# Digital.net
KiCad netlist of a schematic drawn in Altium Designer
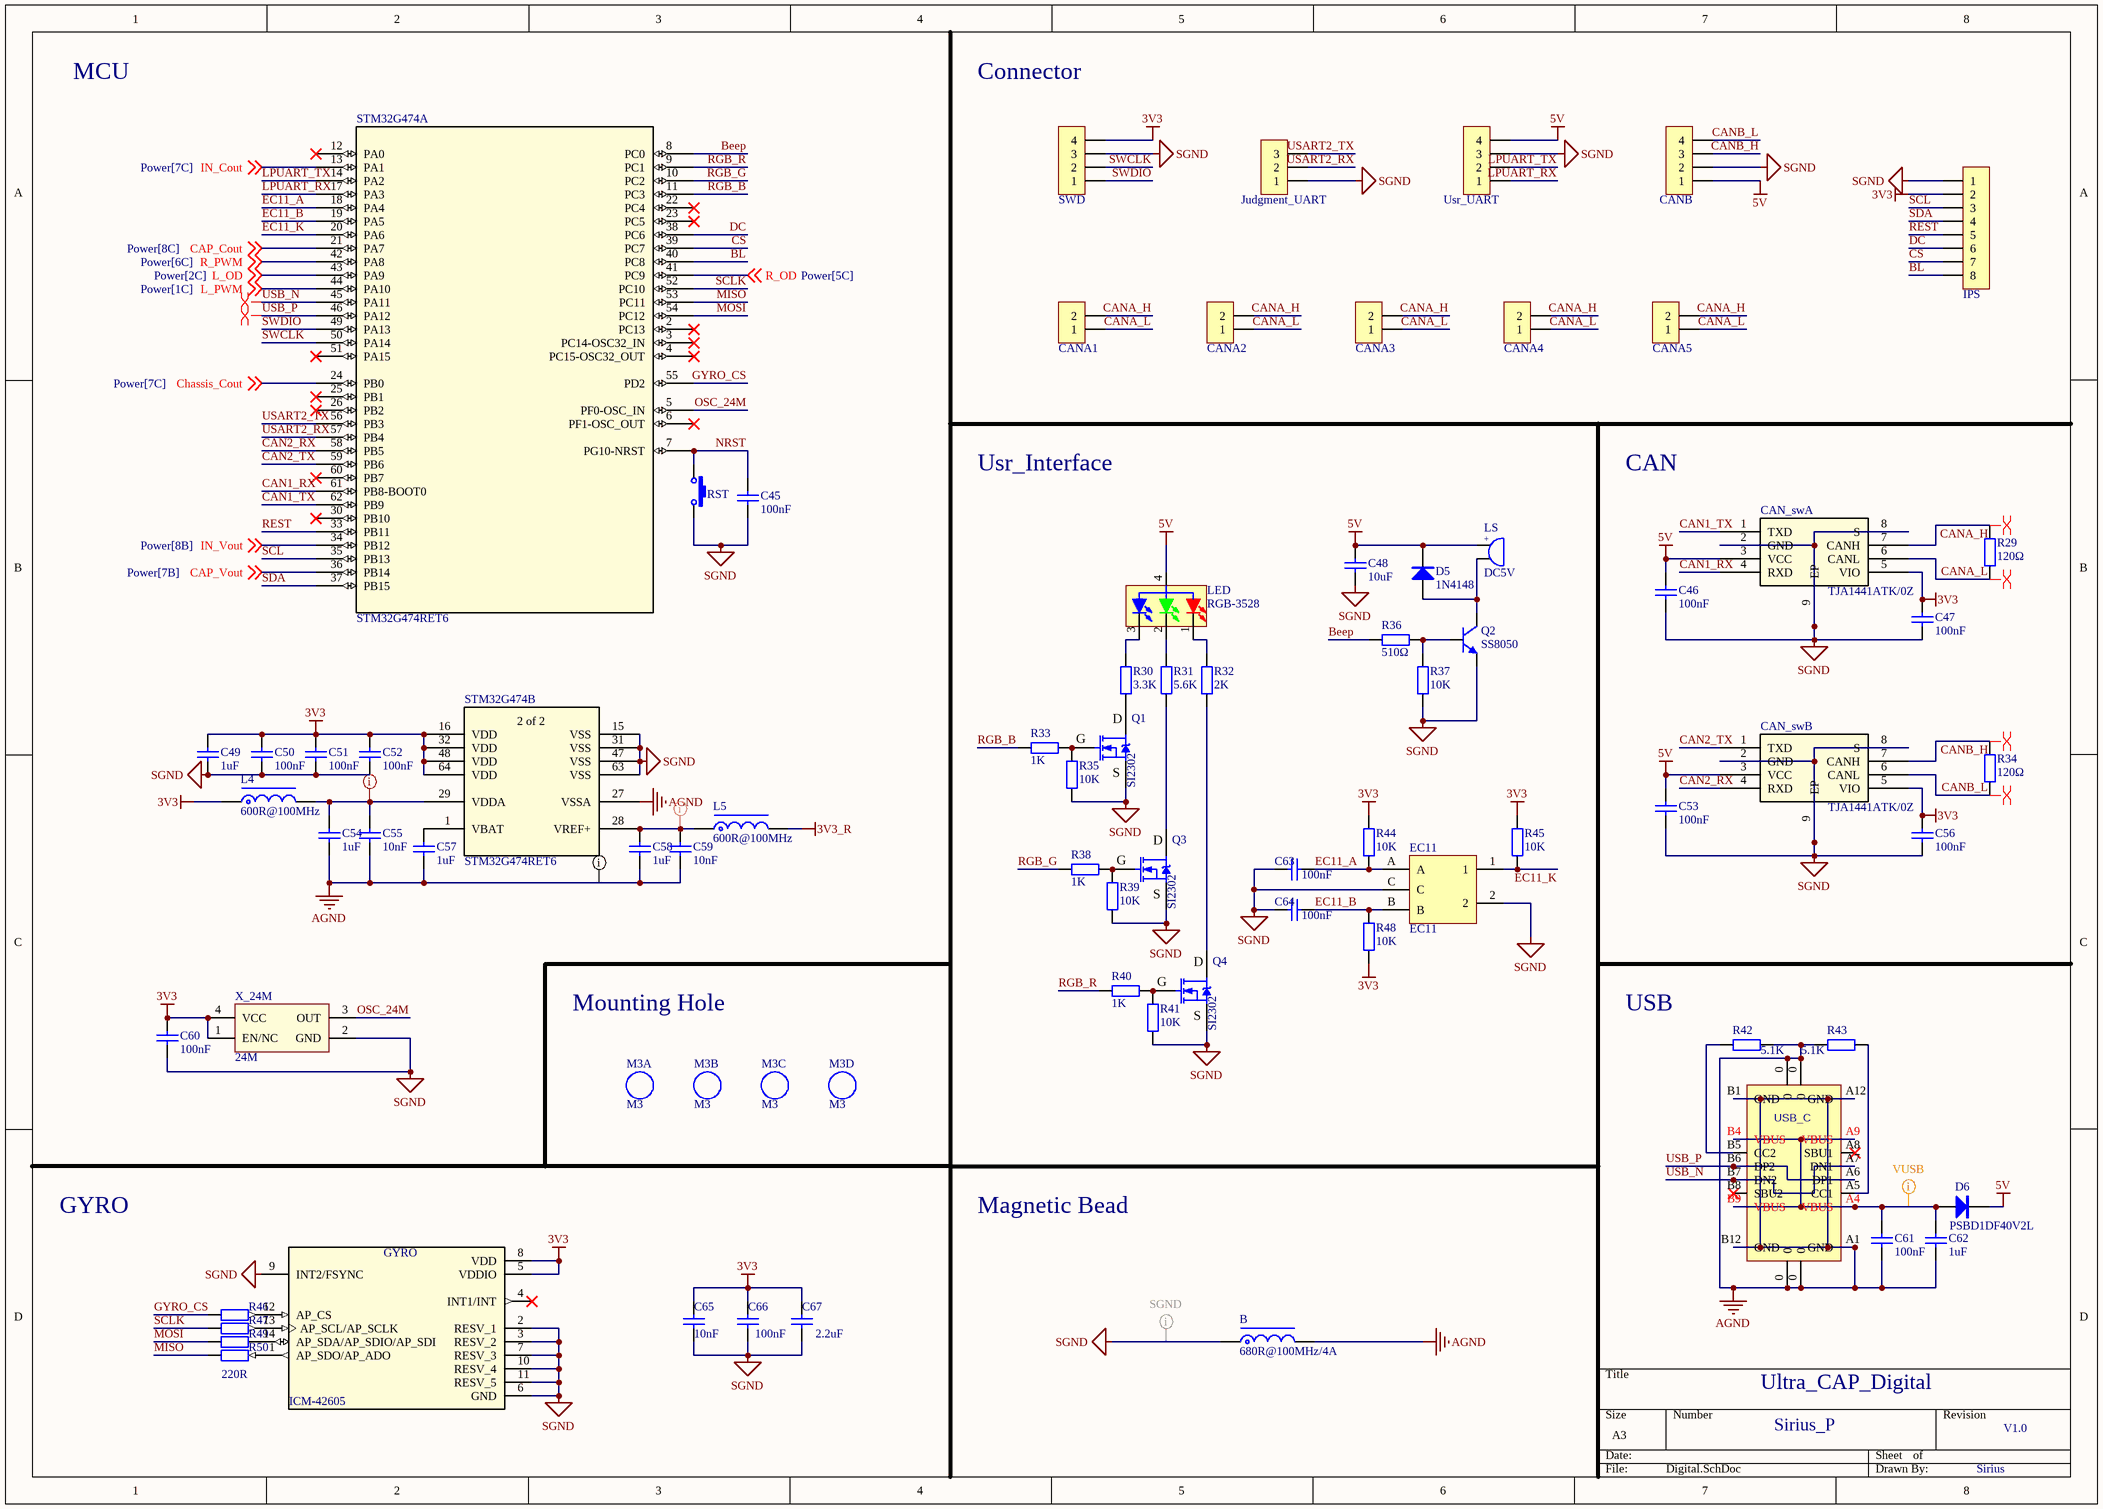
[diagram p0: Digital.SchDoc]

(export (version "E")
  (design (tool "Eeschema 10.0.6"))
  (components
    (comp (ref "B")
      (value "680R@100MHz/4A")
      (footprint "R1812_L")
      (description "磁珠")
      (libsource (lib "0.1 - 电阻-电容-电感-晶振-晶体-磁珠-电位器") (part "FB"))
    )
    (comp (ref "C45")
      (value "100nF")
      (footprint "C0603_L")
      (description "贴片电容")
      (libsource (lib "0.1 - 电阻-电容-电感-晶振-晶体-磁珠-电位器") (part "C"))
    )
    (comp (ref "C46")
      (value "100nF")
      (footprint "C0603_L")
      (description "贴片电容")
      (libsource (lib "0.1 - 电阻-电容-电感-晶振-晶体-磁珠-电位器") (part "C"))
    )
    (comp (ref "C47")
      (value "100nF")
      (footprint "C0603_L")
      (description "贴片电容")
      (libsource (lib "0.1 - 电阻-电容-电感-晶振-晶体-磁珠-电位器") (part "C"))
    )
    (comp (ref "C48")
      (value "10uF")
      (footprint "C0603_L")
      (description "贴片电容")
      (libsource (lib "0.1 - 电阻-电容-电感-晶振-晶体-磁珠-电位器") (part "C"))
    )
    (comp (ref "C49")
      (value "1uF")
      (footprint "C0603_L")
      (description "贴片电容")
      (libsource (lib "0.1 - 电阻-电容-电感-晶振-晶体-磁珠-电位器") (part "C"))
    )
    (comp (ref "C50")
      (value "100nF")
      (footprint "C0603_L")
      (description "贴片电容")
      (libsource (lib "0.1 - 电阻-电容-电感-晶振-晶体-磁珠-电位器") (part "C"))
    )
    (comp (ref "C51")
      (value "100nF")
      (footprint "C0603_L")
      (description "贴片电容")
      (libsource (lib "0.1 - 电阻-电容-电感-晶振-晶体-磁珠-电位器") (part "C"))
    )
    (comp (ref "C52")
      (value "100nF")
      (footprint "C0603_L")
      (description "贴片电容")
      (libsource (lib "0.1 - 电阻-电容-电感-晶振-晶体-磁珠-电位器") (part "C"))
    )
    (comp (ref "C53")
      (value "100nF")
      (footprint "C0603_L")
      (description "贴片电容")
      (libsource (lib "0.1 - 电阻-电容-电感-晶振-晶体-磁珠-电位器") (part "C"))
    )
    (comp (ref "C54")
      (value "1uF")
      (footprint "C0603_L")
      (description "贴片电容")
      (libsource (lib "0.1 - 电阻-电容-电感-晶振-晶体-磁珠-电位器") (part "C"))
    )
    (comp (ref "C55")
      (value "10nF")
      (footprint "C0603_L")
      (description "贴片电容")
      (libsource (lib "0.1 - 电阻-电容-电感-晶振-晶体-磁珠-电位器") (part "C"))
    )
    (comp (ref "C56")
      (value "100nF")
      (footprint "C0603_L")
      (description "贴片电容")
      (libsource (lib "0.1 - 电阻-电容-电感-晶振-晶体-磁珠-电位器") (part "C"))
    )
    (comp (ref "C57")
      (value "1uF")
      (footprint "C0603_L")
      (description "贴片电容")
      (libsource (lib "0.1 - 电阻-电容-电感-晶振-晶体-磁珠-电位器") (part "C"))
    )
    (comp (ref "C58")
      (value "1uF")
      (footprint "C0603_L")
      (description "贴片电容")
      (libsource (lib "0.1 - 电阻-电容-电感-晶振-晶体-磁珠-电位器") (part "C"))
    )
    (comp (ref "C59")
      (value "10nF")
      (footprint "C0603_L")
      (description "贴片电容")
      (libsource (lib "0.1 - 电阻-电容-电感-晶振-晶体-磁珠-电位器") (part "C"))
    )
    (comp (ref "C60")
      (value "100nF")
      (footprint "C0603_L")
      (description "贴片电容")
      (libsource (lib "0.1 - 电阻-电容-电感-晶振-晶体-磁珠-电位器") (part "C"))
    )
    (comp (ref "C61")
      (value "100nF")
      (footprint "C0603_L")
      (description "贴片电容")
      (libsource (lib "0.1 - 电阻-电容-电感-晶振-晶体-磁珠-电位器") (part "C"))
    )
    (comp (ref "C62")
      (value "1uF")
      (footprint "C0603_L")
      (description "贴片电容")
      (libsource (lib "0.1 - 电阻-电容-电感-晶振-晶体-磁珠-电位器") (part "C"))
    )
    (comp (ref "C63")
      (value "100nF")
      (footprint "C0603_L")
      (description "贴片电容")
      (libsource (lib "0.1 - 电阻-电容-电感-晶振-晶体-磁珠-电位器") (part "C"))
    )
    (comp (ref "C64")
      (value "100nF")
      (footprint "C0603_L")
      (description "贴片电容")
      (libsource (lib "0.1 - 电阻-电容-电感-晶振-晶体-磁珠-电位器") (part "C"))
    )
    (comp (ref "C65")
      (value "10nF")
      (footprint "C0603_L")
      (description "VDDIO滤波电容")
      (libsource (lib "0.1 - 电阻-电容-电感-晶振-晶体-磁珠-电位器") (part "C"))
    )
    (comp (ref "C66")
      (value "100nF")
      (footprint "C0603_L")
      (description "VDD滤波电容")
      (libsource (lib "0.1 - 电阻-电容-电感-晶振-晶体-磁珠-电位器") (part "C"))
    )
    (comp (ref "C67")
      (value "2.2uF")
      (footprint "C0603_L")
      (description "VDD滤波电容")
      (libsource (lib "0.1 - 电阻-电容-电感-晶振-晶体-磁珠-电位器") (part "C"))
    )
    (comp (ref "CANA1")
      (value "HDR-1X2")
      (footprint "CONN-SMD_2P-P1.25_JUSHUO_GH125-S02DCA-00")
      (description "2P连接器")
      (libsource (lib "5.1 - 1.25mm连接器(FPC1.25-MX1.25)") (part "Header 2"))
    )
    (comp (ref "CANA2")
      (value "HDR-1X2")
      (footprint "CONN-SMD_2P-P1.25_JUSHUO_GH125-S02DCA-00")
      (description "2P连接器")
      (libsource (lib "5.1 - 1.25mm连接器(FPC1.25-MX1.25)") (part "Header 2"))
    )
    (comp (ref "CANA3")
      (value "HDR-1X2")
      (footprint "CONN-SMD_2P-P1.25_JUSHUO_GH125-S02DCA-00")
      (description "2P连接器")
      (libsource (lib "5.1 - 1.25mm连接器(FPC1.25-MX1.25)") (part "Header 2"))
    )
    (comp (ref "CANA4")
      (value "HDR-1X2")
      (footprint "CONN-SMD_2P-P1.25_JUSHUO_GH125-S02DCA-00")
      (description "2P连接器")
      (libsource (lib "5.1 - 1.25mm连接器(FPC1.25-MX1.25)") (part "Header 2"))
    )
    (comp (ref "CANA5")
      (value "HDR-1X2")
      (footprint "CONN-SMD_2P-P1.25_JUSHUO_GH125-S02DCA-00")
      (description "2P连接器")
      (libsource (lib "5.1 - 1.25mm连接器(FPC1.25-MX1.25)") (part "Header 2"))
    )
    (comp (ref "CANB")
      (value "HDR-1X4")
      (footprint "CONN-SMD_4P-P1.27_GH125-S04DCA-00")
      (description "4P连接器")
      (libsource (lib "5.1 - 1.25mm连接器(FPC1.25-MX1.25)") (part "Header 4"))
    )
    (comp (ref "CAN_swA")
      (value "TJA1441ATK/0Z")
      (footprint "SON65P300X300X100-9N-D")
      (description "CAN电平转换芯片")
      (fields
        (field (name "MANUFACTURER_PART_NUMBER") "TJA1441BTK/0Z")
        (field (name "COPYRIGHT") "Copyright (C) 2022 Ultra Librarian. All rights reserved.")
      )
      (libsource (lib "Extra Sch") (part "TJA1441ATK/0Z"))
    )
    (comp (ref "CAN_swB")
      (value "TJA1441ATK/0Z")
      (footprint "SON65P300X300X100-9N-D")
      (description "CAN电平转换芯片")
      (fields
        (field (name "MANUFACTURER_PART_NUMBER") "TJA1441BTK/0Z")
        (field (name "COPYRIGHT") "Copyright (C) 2022 Ultra Librarian. All rights reserved.")
      )
      (libsource (lib "Extra Sch") (part "TJA1441ATK/0Z"))
    )
    (comp (ref "D5")
      (value "1N4148")
      (footprint "SOD-323")
      (description "开关二极管")
      (libsource (lib "0.2 - 二极管-TVS-ESD-整流桥") (part "1N4148"))
    )
    (comp (ref "D6")
      (value "PSBD1DF40V2L")
      (footprint "SOD-123")
      (description "肖特基二极管")
      (libsource (lib "0.2 - 二极管-TVS-ESD-整流桥") (part "1N5822"))
    )
    (comp (ref "EC11")
      (value "EC11")
      (footprint "EC11")
      (description "数字开关编码器")
      (libsource (lib "0.5 - 按键-开关-蜂鸣器-保险丝-电池-测试点-Mark点") (part "EC11"))
    )
    (comp (ref "GYRO")
      (value "ICM-42605")
      (footprint "PQFN50P300X250X97-14N - duplicate")
      (description "Accelerometer, Gyroscope, 6 Axis Sensor IÂ²C, I3Câ„ , SPI Output")
      (fields (field (name "DIGI-KEY_PART_NUMBER") "1428-1152-1-ND") (field (name "MF") "TDK InvenSense"))
      (libsource (lib "Extra Sch") (part "ICM-42605"))
    )
    (comp (ref "IPS")
      (value "HDR-1X8")
      (footprint "HDR2.54-M-LI-8P")
      (description "8P接插件")
      (libsource (lib "5.5 - 2.54mm(100mil)连接器(XH2.54)") (part "Header 8"))
    )
    (comp (ref "Judgment_UART")
      (value "HDR-1X3")
      (footprint "CONN-SMD_3P-P1.25_JUSHUO_GH125-S03DCA-00")
      (description "3P连接器")
      (libsource (lib "5.1 - 1.25mm连接器(FPC1.25-MX1.25)") (part "Header 3"))
    )
    (comp (ref "L4")
      (value "600R@100MHz")
      (footprint "R0603_L")
      (description "磁珠")
      (libsource (lib "0.1 - 电阻-电容-电感-晶振-晶体-磁珠-电位器") (part "FB"))
    )
    (comp (ref "L5")
      (value "600R@100MHz")
      (footprint "R0603_L")
      (description "磁珠")
      (libsource (lib "0.1 - 电阻-电容-电感-晶振-晶体-磁珠-电位器") (part "FB"))
    )
    (comp (ref "LED")
      (value "RGB-3528")
      (footprint "LED 3528-4Pin")
      (description "3528三基色LED")
      (libsource (lib "0.3 - LED发光二极管-IR二极管_接收管-光耦") (part "LED-RGB 3528"))
    )
    (comp (ref "LS")
      (value "DC5V")
      (footprint "BEEP 5x9x5.5")
      (description "蜂鸣器")
      (libsource (lib "0.5 - 按键-开关-蜂鸣器-保险丝-电池-测试点-Mark点") (part "BEEP"))
    )
    (comp (ref "M3A")
      (value "M3")
      (footprint "M3 125X200")
      (description "铜柱孔")
      (libsource (lib "0.5 - 按键-开关-蜂鸣器-保险丝-电池-测试点-Mark点") (part "M3"))
    )
    (comp (ref "M3B")
      (value "M3")
      (footprint "M3 125X200")
      (description "铜柱孔")
      (libsource (lib "0.5 - 按键-开关-蜂鸣器-保险丝-电池-测试点-Mark点") (part "M3"))
    )
    (comp (ref "M3C")
      (value "M3")
      (footprint "M3 125X200")
      (description "铜柱孔")
      (libsource (lib "0.5 - 按键-开关-蜂鸣器-保险丝-电池-测试点-Mark点") (part "M3"))
    )
    (comp (ref "M3D")
      (value "M3")
      (footprint "M3 125X200")
      (description "铜柱孔")
      (libsource (lib "0.5 - 按键-开关-蜂鸣器-保险丝-电池-测试点-Mark点") (part "M3"))
    )
    (comp (ref "Q1")
      (value "SI2302")
      (footprint "SOT23-3N")
      (description "N沟道 20V/6A")
      (libsource (lib "0.4 - 三极管-场效应管-可控硅") (part "AO3400"))
    )
    (comp (ref "Q2")
      (value "SS8050")
      (footprint "SOT23-3N")
      (description "高频放大-NPN型")
      (libsource (lib "0.4 - 三极管-场效应管-可控硅") (part "8050-SMD"))
    )
    (comp (ref "Q3")
      (value "SI2302")
      (footprint "SOT23-3N")
      (description "N沟道 20V/6A")
      (libsource (lib "0.4 - 三极管-场效应管-可控硅") (part "AO3400"))
    )
    (comp (ref "Q4")
      (value "SI2302")
      (footprint "SOT23-3N")
      (description "N沟道 20V/6A")
      (libsource (lib "0.4 - 三极管-场效应管-可控硅") (part "AO3400"))
    )
    (comp (ref "R29")
      (value "120Ω")
      (footprint "R0603_L")
      (description "贴片电阻")
      (libsource (lib "0.1 - 电阻-电容-电感-晶振-晶体-磁珠-电位器") (part "R"))
    )
    (comp (ref "R30")
      (value "3.3K")
      (footprint "R0603_L")
      (description "贴片电阻")
      (libsource (lib "0.1 - 电阻-电容-电感-晶振-晶体-磁珠-电位器") (part "R"))
    )
    (comp (ref "R31")
      (value "5.6K")
      (footprint "R0603_L")
      (description "贴片电阻")
      (libsource (lib "0.1 - 电阻-电容-电感-晶振-晶体-磁珠-电位器") (part "R"))
    )
    (comp (ref "R32")
      (value "2K")
      (footprint "R0603_L")
      (description "贴片电阻")
      (libsource (lib "0.1 - 电阻-电容-电感-晶振-晶体-磁珠-电位器") (part "R"))
    )
    (comp (ref "R33")
      (value "1K")
      (footprint "R0603_L")
      (description "贴片电阻")
      (libsource (lib "0.1 - 电阻-电容-电感-晶振-晶体-磁珠-电位器") (part "R"))
    )
    (comp (ref "R34")
      (value "120Ω")
      (footprint "R0603_L")
      (description "贴片电阻")
      (libsource (lib "0.1 - 电阻-电容-电感-晶振-晶体-磁珠-电位器") (part "R"))
    )
    (comp (ref "R35")
      (value "10K")
      (footprint "R0603_L")
      (description "贴片电阻")
      (libsource (lib "0.1 - 电阻-电容-电感-晶振-晶体-磁珠-电位器") (part "R"))
    )
    (comp (ref "R36")
      (value "510Ω")
      (footprint "R0603_L")
      (description "贴片电阻")
      (libsource (lib "0.1 - 电阻-电容-电感-晶振-晶体-磁珠-电位器") (part "R"))
    )
    (comp (ref "R37")
      (value "10K")
      (footprint "R0603_L")
      (description "贴片电阻")
      (libsource (lib "0.1 - 电阻-电容-电感-晶振-晶体-磁珠-电位器") (part "R"))
    )
    (comp (ref "R38")
      (value "1K")
      (footprint "R0603_L")
      (description "贴片电阻")
      (libsource (lib "0.1 - 电阻-电容-电感-晶振-晶体-磁珠-电位器") (part "R"))
    )
    (comp (ref "R39")
      (value "10K")
      (footprint "R0603_L")
      (description "贴片电阻")
      (libsource (lib "0.1 - 电阻-电容-电感-晶振-晶体-磁珠-电位器") (part "R"))
    )
    (comp (ref "R40")
      (value "1K")
      (footprint "R0603_L")
      (description "贴片电阻")
      (libsource (lib "0.1 - 电阻-电容-电感-晶振-晶体-磁珠-电位器") (part "R"))
    )
    (comp (ref "R41")
      (value "10K")
      (footprint "R0603_L")
      (description "贴片电阻")
      (libsource (lib "0.1 - 电阻-电容-电感-晶振-晶体-磁珠-电位器") (part "R"))
    )
    (comp (ref "R42")
      (value "5.1K")
      (footprint "R0603_L")
      (description "贴片电阻")
      (libsource (lib "0.1 - 电阻-电容-电感-晶振-晶体-磁珠-电位器") (part "R"))
    )
    (comp (ref "R43")
      (value "5.1K")
      (footprint "R0603_L")
      (description "贴片电阻")
      (libsource (lib "0.1 - 电阻-电容-电感-晶振-晶体-磁珠-电位器") (part "R"))
    )
    (comp (ref "R44")
      (value "10K")
      (footprint "R0603_L")
      (description "贴片电阻")
      (libsource (lib "0.1 - 电阻-电容-电感-晶振-晶体-磁珠-电位器") (part "R"))
    )
    (comp (ref "R45")
      (value "10K")
      (footprint "R0603_L")
      (description "贴片电阻")
      (libsource (lib "0.1 - 电阻-电容-电感-晶振-晶体-磁珠-电位器") (part "R"))
    )
    (comp (ref "R46")
      (value "220R")
      (footprint "R0603_L")
      (description "贴片电阻")
      (libsource (lib "0.1 - 电阻-电容-电感-晶振-晶体-磁珠-电位器") (part "R"))
    )
    (comp (ref "R47")
      (value "220R")
      (footprint "R0603_L")
      (description "贴片电阻")
      (libsource (lib "0.1 - 电阻-电容-电感-晶振-晶体-磁珠-电位器") (part "R"))
    )
    (comp (ref "R48")
      (value "10K")
      (footprint "R0603_L")
      (description "贴片电阻")
      (libsource (lib "0.1 - 电阻-电容-电感-晶振-晶体-磁珠-电位器") (part "R"))
    )
    (comp (ref "R49")
      (value "220R")
      (footprint "R0603_L")
      (description "贴片电阻")
      (libsource (lib "0.1 - 电阻-电容-电感-晶振-晶体-磁珠-电位器") (part "R"))
    )
    (comp (ref "R50")
      (value "220R")
      (footprint "R0603_L")
      (description "贴片电阻")
      (libsource (lib "0.1 - 电阻-电容-电感-晶振-晶体-磁珠-电位器") (part "R"))
    )
    (comp (ref "RST")
      (value "3x6x5")
      (footprint "SW SMD-3*6*5")
      (description "3x6轻触开关")
      (libsource (lib "0.5 - 按键-开关-蜂鸣器-保险丝-电池-测试点-Mark点") (part "SW 3x6"))
    )
    (comp (ref "STM32G474")
      (value "STM32G474RET6")
      (footprint "LQFP64-10*10")
      (description "MCU")
      (fields (field (name "COPYRIGHT") "Copyright (C) 2022 Ultra Librarian. All rights reserved."))
      (libsource (lib "Extra Sch") (part "STM32G474RET6"))
    )
    (comp (ref "SWD")
      (value "HDR-1X4")
      (footprint "MX1.25-WS-4P")
      (description "4P连接器")
      (libsource (lib "5.1 - 1.25mm连接器(FPC1.25-MX1.25)") (part "Header 4"))
    )
    (comp (ref "USB_C")
      (value "TYPE-C 2.0 -16P")
      (footprint "USB-C-SMD_16P")
      (description "USB2.0 Type-C 16Pin  母座")
      (libsource (lib "0.8 - 以太网-音频-Type-C USB插座") (part "USB2.0_Type-C_16Pin"))
    )
    (comp (ref "Usr_UART")
      (value "HDR-1X4")
      (footprint "CONN-SMD_4P-P1.27_GH125-S04DCA-00")
      (description "4P连接器")
      (libsource (lib "5.1 - 1.25mm连接器(FPC1.25-MX1.25)") (part "Header 4"))
    )
    (comp (ref "X_24M")
      (value "24M")
      (footprint "OSC-2025-4P")
      (description "4脚有源晶振(振荡器)")
      (libsource (lib "0.1 - 电阻-电容-电感-晶振-晶体-磁珠-电位器") (part "XTAL-ACT-4P"))
    )
  )
  (nets
    (net (code "1") (name "/BL") (class "Default")
      (node (ref "IPS") (pin "8") (pinfunction "8_8") (pintype "passive"))
      (node (ref "STM32G474") (pin "40") (pinfunction "PC8_40") (pintype "bidirectional"))
    )
    (net (code "2") (name "/Beep") (class "Default")
      (node (ref "R36") (pin "2") (pinfunction "2_2") (pintype "output"))
      (node (ref "STM32G474") (pin "8") (pinfunction "PC0_8") (pintype "bidirectional"))
    )
    (net (code "3") (name "/CAN1_RX") (class "Default")
      (node (ref "CAN_swA") (pin "4") (pinfunction "RXD_4") (pintype "passive"))
      (node (ref "STM32G474") (pin "61") (pinfunction "PB8-BOOT0_61") (pintype "bidirectional"))
    )
    (net (code "4") (name "/CAN1_TX") (class "Default")
      (node (ref "CAN_swA") (pin "1") (pinfunction "TXD_1") (pintype "passive"))
      (node (ref "STM32G474") (pin "62") (pinfunction "PB9_62") (pintype "bidirectional"))
    )
    (net (code "5") (name "/CAN2_RX") (class "Default")
      (node (ref "CAN_swB") (pin "4") (pinfunction "RXD_4") (pintype "passive"))
      (node (ref "STM32G474") (pin "58") (pinfunction "PB5_58") (pintype "bidirectional"))
    )
    (net (code "6") (name "/CAN2_TX") (class "Default")
      (node (ref "CAN_swB") (pin "1") (pinfunction "TXD_1") (pintype "passive"))
      (node (ref "STM32G474") (pin "59") (pinfunction "PB6_59") (pintype "bidirectional"))
    )
    (net (code "7") (name "/CANA_H") (class "Default")
      (node (ref "CANA1") (pin "2") (pinfunction "2_2") (pintype "passive"))
      (node (ref "CANA2") (pin "2") (pinfunction "2_2") (pintype "passive"))
      (node (ref "CANA3") (pin "2") (pinfunction "2_2") (pintype "passive"))
      (node (ref "CANA4") (pin "2") (pinfunction "2_2") (pintype "passive"))
      (node (ref "CANA5") (pin "2") (pinfunction "2_2") (pintype "passive"))
      (node (ref "CAN_swA") (pin "7") (pinfunction "CANH_7") (pintype "passive"))
      (node (ref "R29") (pin "2") (pinfunction "2_2") (pintype "output"))
    )
    (net (code "8") (name "/CANA_L") (class "Default")
      (node (ref "CANA1") (pin "1") (pinfunction "1_1") (pintype "passive"))
      (node (ref "CANA2") (pin "1") (pinfunction "1_1") (pintype "passive"))
      (node (ref "CANA3") (pin "1") (pinfunction "1_1") (pintype "passive"))
      (node (ref "CANA4") (pin "1") (pinfunction "1_1") (pintype "passive"))
      (node (ref "CANA5") (pin "1") (pinfunction "1_1") (pintype "passive"))
      (node (ref "CAN_swA") (pin "6") (pinfunction "CANL_6") (pintype "passive"))
      (node (ref "R29") (pin "1") (pinfunction "1_1") (pintype "passive"))
    )
    (net (code "9") (name "/CANB_H") (class "Default")
      (node (ref "CANB") (pin "3") (pinfunction "3_3") (pintype "passive"))
      (node (ref "CAN_swB") (pin "7") (pinfunction "CANH_7") (pintype "passive"))
      (node (ref "R34") (pin "2") (pinfunction "2_2") (pintype "output"))
    )
    (net (code "10") (name "/CANB_L") (class "Default")
      (node (ref "CANB") (pin "4") (pinfunction "4_4") (pintype "passive"))
      (node (ref "CAN_swB") (pin "6") (pinfunction "CANL_6") (pintype "passive"))
      (node (ref "R34") (pin "1") (pinfunction "1_1") (pintype "passive"))
    )
    (net (code "11") (name "/CS") (class "Default")
      (node (ref "IPS") (pin "7") (pinfunction "7_7") (pintype "passive"))
      (node (ref "STM32G474") (pin "39") (pinfunction "PC7_39") (pintype "bidirectional"))
    )
    (net (code "12") (name "/DC") (class "Default")
      (node (ref "IPS") (pin "6") (pinfunction "6_6") (pintype "passive"))
      (node (ref "STM32G474") (pin "38") (pinfunction "PC6_38") (pintype "bidirectional"))
    )
    (net (code "13") (name "/EC11_A") (class "Default")
      (node (ref "C63") (pin "2") (pinfunction "2_2") (pintype "passive"))
      (node (ref "EC11") (pin "A") (pinfunction "A_A") (pintype "passive"))
      (node (ref "R44") (pin "2") (pinfunction "2_2") (pintype "output"))
      (node (ref "STM32G474") (pin "18") (pinfunction "PA4_18") (pintype "bidirectional"))
    )
    (net (code "14") (name "/EC11_B") (class "Default")
      (node (ref "C64") (pin "2") (pinfunction "2_2") (pintype "passive"))
      (node (ref "EC11") (pin "B") (pinfunction "B_B") (pintype "passive"))
      (node (ref "R48") (pin "1") (pinfunction "1_1") (pintype "passive"))
      (node (ref "STM32G474") (pin "19") (pinfunction "PA5_19") (pintype "bidirectional"))
    )
    (net (code "15") (name "/EC11_K") (class "Default")
      (node (ref "EC11") (pin "1") (pinfunction "1_1") (pintype "passive"))
      (node (ref "R45") (pin "2") (pinfunction "2_2") (pintype "output"))
      (node (ref "STM32G474") (pin "20") (pinfunction "PA6_20") (pintype "bidirectional"))
    )
    (net (code "16") (name "/GYRO_CS") (class "Default")
      (node (ref "R46") (pin "1") (pinfunction "1_1") (pintype "passive"))
      (node (ref "STM32G474") (pin "55") (pinfunction "PD2_55") (pintype "bidirectional"))
    )
    (net (code "17") (name "/LPUART_RX") (class "Default")
      (node (ref "STM32G474") (pin "17") (pinfunction "PA3_17") (pintype "bidirectional"))
      (node (ref "Usr_UART") (pin "1") (pinfunction "1_1") (pintype "passive"))
    )
    (net (code "18") (name "/LPUART_TX") (class "Default")
      (node (ref "STM32G474") (pin "14") (pinfunction "PA2_14") (pintype "bidirectional"))
      (node (ref "Usr_UART") (pin "2") (pinfunction "2_2") (pintype "passive"))
    )
    (net (code "19") (name "/MISO") (class "Default")
      (node (ref "R50") (pin "1") (pinfunction "1_1") (pintype "passive"))
      (node (ref "STM32G474") (pin "53") (pinfunction "PC11_53") (pintype "bidirectional"))
    )
    (net (code "20") (name "/MOSI") (class "Default")
      (node (ref "R49") (pin "1") (pinfunction "1_1") (pintype "passive"))
      (node (ref "STM32G474") (pin "54") (pinfunction "PC12_54") (pintype "bidirectional"))
    )
    (net (code "21") (name "/NRST") (class "Default")
      (node (ref "C45") (pin "2") (pinfunction "2_2") (pintype "passive"))
      (node (ref "RST") (pin "1") (pinfunction "1_1") (pintype "passive"))
      (node (ref "STM32G474") (pin "7") (pinfunction "PG10-NRST_7") (pintype "bidirectional"))
    )
    (net (code "22") (name "/OSC_24M") (class "Default")
      (node (ref "STM32G474") (pin "5") (pinfunction "PF0-OSC_IN_5") (pintype "bidirectional"))
      (node (ref "X_24M") (pin "3") (pinfunction "OUT_3") (pintype "passive"))
    )
    (net (code "23") (name "/REST") (class "Default")
      (node (ref "IPS") (pin "5") (pinfunction "5_5") (pintype "passive"))
      (node (ref "STM32G474") (pin "33") (pinfunction "PB11_33") (pintype "bidirectional"))
    )
    (net (code "24") (name "/RGB_B") (class "Default")
      (node (ref "R33") (pin "2") (pinfunction "2_2") (pintype "output"))
      (node (ref "STM32G474") (pin "11") (pinfunction "PC3_11") (pintype "bidirectional"))
    )
    (net (code "25") (name "/RGB_G") (class "Default")
      (node (ref "R38") (pin "2") (pinfunction "2_2") (pintype "output"))
      (node (ref "STM32G474") (pin "10") (pinfunction "PC2_10") (pintype "bidirectional"))
    )
    (net (code "26") (name "/RGB_R") (class "Default")
      (node (ref "R40") (pin "2") (pinfunction "2_2") (pintype "output"))
      (node (ref "STM32G474") (pin "9") (pinfunction "PC1_9") (pintype "bidirectional"))
    )
    (net (code "27") (name "/SCL") (class "Default")
      (node (ref "IPS") (pin "3") (pinfunction "3_3") (pintype "passive"))
      (node (ref "STM32G474") (pin "35") (pinfunction "PB13_35") (pintype "bidirectional"))
    )
    (net (code "28") (name "/SCLK") (class "Default")
      (node (ref "R47") (pin "1") (pinfunction "1_1") (pintype "passive"))
      (node (ref "STM32G474") (pin "52") (pinfunction "PC10_52") (pintype "bidirectional"))
    )
    (net (code "29") (name "/SDA") (class "Default")
      (node (ref "IPS") (pin "4") (pinfunction "4_4") (pintype "passive"))
      (node (ref "STM32G474") (pin "37") (pinfunction "PB15_37") (pintype "bidirectional"))
    )
    (net (code "30") (name "/SWCLK") (class "Default")
      (node (ref "STM32G474") (pin "50") (pinfunction "PA14_50") (pintype "bidirectional"))
      (node (ref "SWD") (pin "2") (pinfunction "2_2") (pintype "passive"))
    )
    (net (code "31") (name "/SWDIO") (class "Default")
      (node (ref "STM32G474") (pin "49") (pinfunction "PA13_49") (pintype "bidirectional"))
      (node (ref "SWD") (pin "1") (pinfunction "1_1") (pintype "passive"))
    )
    (net (code "32") (name "/USART2_RX") (class "Default")
      (node (ref "Judgment_UART") (pin "2") (pinfunction "2_2") (pintype "passive"))
      (node (ref "STM32G474") (pin "57") (pinfunction "PB4_57") (pintype "bidirectional"))
    )
    (net (code "33") (name "/USART2_TX") (class "Default")
      (node (ref "Judgment_UART") (pin "3") (pinfunction "3_3") (pintype "passive"))
      (node (ref "STM32G474") (pin "56") (pinfunction "PB3_56") (pintype "bidirectional"))
    )
    (net (code "34") (name "/USB_N") (class "Default")
      (node (ref "STM32G474") (pin "45") (pinfunction "PA11_45") (pintype "bidirectional"))
      (node (ref "USB_C") (pin "A7") (pinfunction "DN1_A7") (pintype "passive"))
      (node (ref "USB_C") (pin "B7") (pinfunction "DN2_B7") (pintype "passive"))
    )
    (net (code "35") (name "/USB_P") (class "Default")
      (node (ref "STM32G474") (pin "46") (pinfunction "PA12_46") (pintype "bidirectional"))
      (node (ref "USB_C") (pin "A6") (pinfunction "DP1_A6") (pintype "passive"))
      (node (ref "USB_C") (pin "B6") (pinfunction "DP2_B6") (pintype "passive"))
    )
    (net (code "36") (name "3V3") (class "Default")
      (node (ref "C47") (pin "2") (pinfunction "2_2") (pintype "passive"))
      (node (ref "C49") (pin "2") (pinfunction "2_2") (pintype "passive"))
      (node (ref "C50") (pin "2") (pinfunction "2_2") (pintype "passive"))
      (node (ref "C51") (pin "2") (pinfunction "2_2") (pintype "passive"))
      (node (ref "C52") (pin "1") (pinfunction "1_1") (pintype "passive"))
      (node (ref "C56") (pin "2") (pinfunction "2_2") (pintype "passive"))
      (node (ref "C60") (pin "2") (pinfunction "2_2") (pintype "passive"))
      (node (ref "C65") (pin "2") (pinfunction "2_2") (pintype "passive"))
      (node (ref "C66") (pin "2") (pinfunction "2_2") (pintype "passive"))
      (node (ref "C67") (pin "2") (pinfunction "2_2") (pintype "passive"))
      (node (ref "CAN_swA") (pin "5") (pinfunction "VIO_5") (pintype "passive"))
      (node (ref "CAN_swB") (pin "5") (pinfunction "VIO_5") (pintype "passive"))
      (node (ref "GYRO") (pin "5") (pinfunction "VDDIO_5") (pintype "power_in"))
      (node (ref "GYRO") (pin "8") (pinfunction "VDD_8") (pintype "power_in"))
      (node (ref "IPS") (pin "2") (pinfunction "2_2") (pintype "passive"))
      (node (ref "L4") (pin "1") (pinfunction "1_1") (pintype "passive"))
      (node (ref "R44") (pin "1") (pinfunction "1_1") (pintype "passive"))
      (node (ref "R45") (pin "1") (pinfunction "1_1") (pintype "passive"))
      (node (ref "R48") (pin "2") (pinfunction "2_2") (pintype "output"))
      (node (ref "STM32G474") (pin "16") (pinfunction "VDD_16") (pintype "power_in"))
      (node (ref "STM32G474") (pin "32") (pinfunction "VDD_32") (pintype "power_in"))
      (node (ref "STM32G474") (pin "48") (pinfunction "VDD_48") (pintype "power_in"))
      (node (ref "STM32G474") (pin "64") (pinfunction "VDD_64") (pintype "power_in"))
      (node (ref "SWD") (pin "4") (pinfunction "4_4") (pintype "passive"))
      (node (ref "X_24M") (pin "1") (pinfunction "EN/NC_1") (pintype "passive"))
      (node (ref "X_24M") (pin "4") (pinfunction "VCC_4") (pintype "passive"))
    )
    (net (code "37") (name "3V3_R") (class "Default")
      (node (ref "L5") (pin "2") (pinfunction "2_2") (pintype "passive"))
    )
    (net (code "38") (name "5V") (class "Default")
      (node (ref "C46") (pin "2") (pinfunction "2_2") (pintype "passive"))
      (node (ref "C48") (pin "2") (pinfunction "2_2") (pintype "passive"))
      (node (ref "C53") (pin "2") (pinfunction "2_2") (pintype "passive"))
      (node (ref "CANB") (pin "1") (pinfunction "1_1") (pintype "passive"))
      (node (ref "CAN_swA") (pin "3") (pinfunction "VCC_3") (pintype "power_in"))
      (node (ref "CAN_swB") (pin "3") (pinfunction "VCC_3") (pintype "power_in"))
      (node (ref "D5") (pin "2") (pinfunction "K_2") (pintype "passive"))
      (node (ref "D6") (pin "2") (pinfunction "K_2") (pintype "passive"))
      (node (ref "LED") (pin "4") (pinfunction "A_4") (pintype "passive"))
      (node (ref "LS") (pin "1") (pinfunction "1_1") (pintype "passive"))
      (node (ref "Usr_UART") (pin "4") (pinfunction "4_4") (pintype "passive"))
    )
    (net (code "39") (name "AGND") (class "Default")
      (node (ref "B") (pin "2") (pinfunction "2_2") (pintype "passive"))
      (node (ref "C54") (pin "1") (pinfunction "1_1") (pintype "passive"))
      (node (ref "C55") (pin "1") (pinfunction "1_1") (pintype "passive"))
      (node (ref "C57") (pin "1") (pinfunction "1_1") (pintype "passive"))
      (node (ref "C58") (pin "1") (pinfunction "1_1") (pintype "passive"))
      (node (ref "C59") (pin "1") (pinfunction "1_1") (pintype "passive"))
      (node (ref "C61") (pin "1") (pinfunction "1_1") (pintype "passive"))
      (node (ref "C62") (pin "1") (pinfunction "1_1") (pintype "passive"))
      (node (ref "R42") (pin "2") (pinfunction "2_2") (pintype "output"))
      (node (ref "R43") (pin "1") (pinfunction "1_1") (pintype "passive"))
      (node (ref "STM32G474") (pin "27") (pinfunction "VSSA_27") (pintype "power_in"))
      (node (ref "USB_C") (pin "0") (pinfunction "0_0") (pintype "passive"))
      (node (ref "USB_C") (pin "A1") (pinfunction "GND_A1") (pintype "passive"))
      (node (ref "USB_C") (pin "A12") (pinfunction "GND_A12") (pintype "passive"))
      (node (ref "USB_C") (pin "B1") (pinfunction "GND_B1") (pintype "passive"))
      (node (ref "USB_C") (pin "B12") (pinfunction "GND_B12") (pintype "passive"))
    )
    (net (code "40") (name "CAP_Cout") (class "Default")
      (node (ref "STM32G474") (pin "21") (pinfunction "PA7_21") (pintype "bidirectional"))
    )
    (net (code "41") (name "CAP_Vout") (class "Default")
      (node (ref "STM32G474") (pin "36") (pinfunction "PB14_36") (pintype "bidirectional"))
    )
    (net (code "42") (name "Chassis_Cout") (class "Default")
      (node (ref "STM32G474") (pin "24") (pinfunction "PB0_24") (pintype "bidirectional"))
    )
    (net (code "43") (name "IN_Cout") (class "Default")
      (node (ref "STM32G474") (pin "13") (pinfunction "PA1_13") (pintype "bidirectional"))
    )
    (net (code "44") (name "IN_Vout") (class "Default")
      (node (ref "STM32G474") (pin "34") (pinfunction "PB12_34") (pintype "bidirectional"))
    )
    (net (code "45") (name "L_OD") (class "Default")
      (node (ref "STM32G474") (pin "43") (pinfunction "PA9_43") (pintype "bidirectional"))
    )
    (net (code "46") (name "L_PWM") (class "Default")
      (node (ref "STM32G474") (pin "44") (pinfunction "PA10_44") (pintype "bidirectional"))
    )
    (net (code "47") (name "Net-(D5-A)") (class "Default")
      (node (ref "D5") (pin "1") (pinfunction "A_1") (pintype "passive"))
      (node (ref "LS") (pin "2") (pinfunction "2_2") (pintype "passive"))
      (node (ref "Q2") (pin "3") (pinfunction "C_3") (pintype "passive"))
    )
    (net (code "48") (name "Net-(D6-A)") (class "Default")
      (node (ref "C61") (pin "2") (pinfunction "2_2") (pintype "passive"))
      (node (ref "C62") (pin "2") (pinfunction "2_2") (pintype "passive"))
      (node (ref "D6") (pin "1") (pinfunction "A_1") (pintype "passive"))
      (node (ref "USB_C") (pin "A4") (pinfunction "VBUS_A4") (pintype "passive"))
      (node (ref "USB_C") (pin "A9") (pinfunction "VBUS_A9") (pintype "passive"))
      (node (ref "USB_C") (pin "B4") (pinfunction "VBUS_B4") (pintype "passive"))
      (node (ref "USB_C") (pin "B9") (pinfunction "VBUS_B9") (pintype "passive"))
    )
    (net (code "49") (name "Net-(GYRO-AP_CS)") (class "Default")
      (node (ref "GYRO") (pin "12") (pinfunction "AP_CS_12") (pintype "input"))
      (node (ref "R46") (pin "2") (pinfunction "2_2") (pintype "output"))
    )
    (net (code "50") (name "Net-(GYRO-AP_SCL{slash}AP_SCLK)") (class "Default")
      (node (ref "GYRO") (pin "13") (pinfunction "AP_SCL/AP_SCLK_13") (pintype "input"))
      (node (ref "R47") (pin "2") (pinfunction "2_2") (pintype "output"))
    )
    (net (code "51") (name "Net-(GYRO-AP_SDA{slash}AP_SDIO{slash}AP_SDI)") (class "Default")
      (node (ref "GYRO") (pin "14") (pinfunction "AP_SDA/AP_SDIO/AP_SDI_14") (pintype "bidirectional"))
      (node (ref "R49") (pin "2") (pinfunction "2_2") (pintype "output"))
    )
    (net (code "52") (name "Net-(GYRO-AP_SDO{slash}AP_ADO)") (class "Default")
      (node (ref "GYRO") (pin "1") (pinfunction "AP_SDO/AP_ADO_1") (pintype "output"))
      (node (ref "R50") (pin "2") (pinfunction "2_2") (pintype "output"))
    )
    (net (code "53") (name "Net-(LED-BULE_K)") (class "Default")
      (node (ref "LED") (pin "3") (pinfunction "BULE_K_3") (pintype "passive"))
      (node (ref "R30") (pin "2") (pinfunction "2_2") (pintype "output"))
    )
    (net (code "54") (name "Net-(LED-GREEN_K)") (class "Default")
      (node (ref "LED") (pin "2") (pinfunction "GREEN_K_2") (pintype "passive"))
      (node (ref "R31") (pin "2") (pinfunction "2_2") (pintype "output"))
    )
    (net (code "55") (name "Net-(LED-RED_K)") (class "Default")
      (node (ref "LED") (pin "1") (pinfunction "RED_K_1") (pintype "passive"))
      (node (ref "R32") (pin "2") (pinfunction "2_2") (pintype "output"))
    )
    (net (code "56") (name "Net-(Q1-D)") (class "Default")
      (node (ref "Q1") (pin "3") (pinfunction "D_3") (pintype "passive"))
      (node (ref "R30") (pin "1") (pinfunction "1_1") (pintype "passive"))
    )
    (net (code "57") (name "Net-(Q1-G)") (class "Default")
      (node (ref "Q1") (pin "1") (pinfunction "G_1") (pintype "passive"))
      (node (ref "R33") (pin "1") (pinfunction "1_1") (pintype "passive"))
      (node (ref "R35") (pin "1") (pinfunction "1_1") (pintype "passive"))
    )
    (net (code "58") (name "Net-(Q2-B)") (class "Default")
      (node (ref "Q2") (pin "1") (pinfunction "B_1") (pintype "passive"))
      (node (ref "R36") (pin "1") (pinfunction "1_1") (pintype "passive"))
      (node (ref "R37") (pin "1") (pinfunction "1_1") (pintype "passive"))
    )
    (net (code "59") (name "Net-(Q3-D)") (class "Default")
      (node (ref "Q3") (pin "3") (pinfunction "D_3") (pintype "passive"))
      (node (ref "R31") (pin "1") (pinfunction "1_1") (pintype "passive"))
    )
    (net (code "60") (name "Net-(Q3-G)") (class "Default")
      (node (ref "Q3") (pin "1") (pinfunction "G_1") (pintype "passive"))
      (node (ref "R38") (pin "1") (pinfunction "1_1") (pintype "passive"))
      (node (ref "R39") (pin "1") (pinfunction "1_1") (pintype "passive"))
    )
    (net (code "61") (name "Net-(Q4-D)") (class "Default")
      (node (ref "Q4") (pin "3") (pinfunction "D_3") (pintype "passive"))
      (node (ref "R32") (pin "1") (pinfunction "1_1") (pintype "passive"))
    )
    (net (code "62") (name "Net-(Q4-G)") (class "Default")
      (node (ref "Q4") (pin "1") (pinfunction "G_1") (pintype "passive"))
      (node (ref "R40") (pin "1") (pinfunction "1_1") (pintype "passive"))
      (node (ref "R41") (pin "1") (pinfunction "1_1") (pintype "passive"))
    )
    (net (code "63") (name "Net-(STM32G474B-VBAT)") (class "Default")
      (node (ref "C57") (pin "2") (pinfunction "2_2") (pintype "passive"))
      (node (ref "STM32G474") (pin "1") (pinfunction "VBAT_1") (pintype "power_in"))
    )
    (net (code "64") (name "Net-(STM32G474B-VDDA)") (class "Default")
      (node (ref "C54") (pin "2") (pinfunction "2_2") (pintype "passive"))
      (node (ref "C55") (pin "2") (pinfunction "2_2") (pintype "passive"))
      (node (ref "L4") (pin "2") (pinfunction "2_2") (pintype "passive"))
      (node (ref "STM32G474") (pin "29") (pinfunction "VDDA_29") (pintype "power_in"))
    )
    (net (code "65") (name "Net-(STM32G474B-VREF+)") (class "Default")
      (node (ref "C58") (pin "2") (pinfunction "2_2") (pintype "passive"))
      (node (ref "C59") (pin "2") (pinfunction "2_2") (pintype "passive"))
      (node (ref "L5") (pin "1") (pinfunction "1_1") (pintype "passive"))
      (node (ref "STM32G474") (pin "28") (pinfunction "VREF+_28") (pintype "power_in"))
    )
    (net (code "66") (name "Net-(USB_C-CC1)") (class "Default")
      (node (ref "R43") (pin "2") (pinfunction "2_2") (pintype "output"))
      (node (ref "USB_C") (pin "A5") (pinfunction "CC1_A5") (pintype "passive"))
    )
    (net (code "67") (name "Net-(USB_C-CC2)") (class "Default")
      (node (ref "R42") (pin "1") (pinfunction "1_1") (pintype "passive"))
      (node (ref "USB_C") (pin "B5") (pinfunction "CC2_B5") (pintype "passive"))
    )
    (net (code "68") (name "R_OD") (class "Default")
      (node (ref "STM32G474") (pin "41") (pinfunction "PC9_41") (pintype "bidirectional"))
    )
    (net (code "69") (name "R_PWM") (class "Default")
      (node (ref "STM32G474") (pin "42") (pinfunction "PA8_42") (pintype "bidirectional"))
    )
    (net (code "70") (name "SGND") (class "Default")
      (node (ref "B") (pin "1") (pinfunction "1_1") (pintype "passive"))
      (node (ref "C45") (pin "1") (pinfunction "1_1") (pintype "passive"))
      (node (ref "C46") (pin "1") (pinfunction "1_1") (pintype "passive"))
      (node (ref "C47") (pin "1") (pinfunction "1_1") (pintype "passive"))
      (node (ref "C48") (pin "1") (pinfunction "1_1") (pintype "passive"))
      (node (ref "C49") (pin "1") (pinfunction "1_1") (pintype "passive"))
      (node (ref "C50") (pin "1") (pinfunction "1_1") (pintype "passive"))
      (node (ref "C51") (pin "1") (pinfunction "1_1") (pintype "passive"))
      (node (ref "C52") (pin "2") (pinfunction "2_2") (pintype "passive"))
      (node (ref "C53") (pin "1") (pinfunction "1_1") (pintype "passive"))
      (node (ref "C56") (pin "1") (pinfunction "1_1") (pintype "passive"))
      (node (ref "C60") (pin "1") (pinfunction "1_1") (pintype "passive"))
      (node (ref "C63") (pin "1") (pinfunction "1_1") (pintype "passive"))
      (node (ref "C64") (pin "1") (pinfunction "1_1") (pintype "passive"))
      (node (ref "C65") (pin "1") (pinfunction "1_1") (pintype "passive"))
      (node (ref "C66") (pin "1") (pinfunction "1_1") (pintype "passive"))
      (node (ref "C67") (pin "1") (pinfunction "1_1") (pintype "passive"))
      (node (ref "CANB") (pin "2") (pinfunction "2_2") (pintype "passive"))
      (node (ref "CAN_swA") (pin "2") (pinfunction "GND_2") (pintype "passive"))
      (node (ref "CAN_swA") (pin "8") (pinfunction "S_8") (pintype "passive"))
      (node (ref "CAN_swA") (pin "9") (pinfunction "EP_9") (pintype "passive"))
      (node (ref "CAN_swB") (pin "2") (pinfunction "GND_2") (pintype "passive"))
      (node (ref "CAN_swB") (pin "8") (pinfunction "S_8") (pintype "passive"))
      (node (ref "CAN_swB") (pin "9") (pinfunction "EP_9") (pintype "passive"))
      (node (ref "EC11") (pin "2") (pinfunction "2_2") (pintype "passive"))
      (node (ref "EC11") (pin "C") (pinfunction "C_C") (pintype "passive"))
      (node (ref "GYRO") (pin "10") (pinfunction "RESV_4_10") (pintype "passive"))
      (node (ref "GYRO") (pin "11") (pinfunction "RESV_5_11") (pintype "passive"))
      (node (ref "GYRO") (pin "2") (pinfunction "RESV_1_2") (pintype "passive"))
      (node (ref "GYRO") (pin "3") (pinfunction "RESV_2_3") (pintype "passive"))
      (node (ref "GYRO") (pin "6") (pinfunction "GND_6") (pintype "power_in"))
      (node (ref "GYRO") (pin "7") (pinfunction "RESV_3_7") (pintype "passive"))
      (node (ref "GYRO") (pin "9") (pinfunction "INT2/FSYNC_9") (pintype "passive"))
      (node (ref "IPS") (pin "1") (pinfunction "1_1") (pintype "passive"))
      (node (ref "Judgment_UART") (pin "1") (pinfunction "1_1") (pintype "passive"))
      (node (ref "Q1") (pin "2") (pinfunction "S_2") (pintype "passive"))
      (node (ref "Q2") (pin "2") (pinfunction "E_2") (pintype "passive"))
      (node (ref "Q3") (pin "2") (pinfunction "S_2") (pintype "passive"))
      (node (ref "Q4") (pin "2") (pinfunction "S_2") (pintype "passive"))
      (node (ref "R35") (pin "2") (pinfunction "2_2") (pintype "output"))
      (node (ref "R37") (pin "2") (pinfunction "2_2") (pintype "output"))
      (node (ref "R39") (pin "2") (pinfunction "2_2") (pintype "output"))
      (node (ref "R41") (pin "2") (pinfunction "2_2") (pintype "output"))
      (node (ref "RST") (pin "2") (pinfunction "2_2") (pintype "passive"))
      (node (ref "STM32G474") (pin "15") (pinfunction "VSS_15") (pintype "power_in"))
      (node (ref "STM32G474") (pin "31") (pinfunction "VSS_31") (pintype "power_in"))
      (node (ref "STM32G474") (pin "47") (pinfunction "VSS_47") (pintype "power_in"))
      (node (ref "STM32G474") (pin "63") (pinfunction "VSS_63") (pintype "power_in"))
      (node (ref "SWD") (pin "3") (pinfunction "3_3") (pintype "passive"))
      (node (ref "Usr_UART") (pin "3") (pinfunction "3_3") (pintype "passive"))
      (node (ref "X_24M") (pin "2") (pinfunction "GND_2") (pintype "passive"))
    )
    (net (code "71") (name "unconnected-(GYRO-INT1{slash}INT-Pad4)") (class "Default")
      (node (ref "GYRO") (pin "4") (pinfunction "INT1/INT_4") (pintype "output+no_connect"))
    )
    (net (code "72") (name "unconnected-(STM32G474A-PA0-Pad12)") (class "Default")
      (node (ref "STM32G474") (pin "12") (pinfunction "PA0_12") (pintype "bidirectional+no_connect"))
    )
    (net (code "73") (name "unconnected-(STM32G474A-PA15-Pad51)") (class "Default")
      (node (ref "STM32G474") (pin "51") (pinfunction "PA15_51") (pintype "bidirectional+no_connect"))
    )
    (net (code "74") (name "unconnected-(STM32G474A-PB1-Pad25)") (class "Default")
      (node (ref "STM32G474") (pin "25") (pinfunction "PB1_25") (pintype "bidirectional+no_connect"))
    )
    (net (code "75") (name "unconnected-(STM32G474A-PB2-Pad26)") (class "Default")
      (node (ref "STM32G474") (pin "26") (pinfunction "PB2_26") (pintype "bidirectional+no_connect"))
    )
    (net (code "76") (name "unconnected-(STM32G474A-PB7-Pad60)") (class "Default")
      (node (ref "STM32G474") (pin "60") (pinfunction "PB7_60") (pintype "bidirectional+no_connect"))
    )
    (net (code "77") (name "unconnected-(STM32G474A-PB10-Pad30)") (class "Default")
      (node (ref "STM32G474") (pin "30") (pinfunction "PB10_30") (pintype "bidirectional+no_connect"))
    )
    (net (code "78") (name "unconnected-(STM32G474A-PC4-Pad22)") (class "Default")
      (node (ref "STM32G474") (pin "22") (pinfunction "PC4_22") (pintype "bidirectional+no_connect"))
    )
    (net (code "79") (name "unconnected-(STM32G474A-PC5-Pad23)") (class "Default")
      (node (ref "STM32G474") (pin "23") (pinfunction "PC5_23") (pintype "bidirectional+no_connect"))
    )
    (net (code "80") (name "unconnected-(STM32G474A-PC13-Pad2)") (class "Default")
      (node (ref "STM32G474") (pin "2") (pinfunction "PC13_2") (pintype "bidirectional+no_connect"))
    )
    (net (code "81") (name "unconnected-(STM32G474A-PC14-OSC32_IN-Pad3)") (class "Default")
      (node (ref "STM32G474") (pin "3") (pinfunction "PC14-OSC32_IN_3") (pintype "bidirectional+no_connect"))
    )
    (net (code "82") (name "unconnected-(STM32G474A-PC15-OSC32_OUT-Pad4)") (class "Default")
      (node (ref "STM32G474") (pin "4") (pinfunction "PC15-OSC32_OUT_4") (pintype "bidirectional+no_connect"))
    )
    (net (code "83") (name "unconnected-(STM32G474A-PF1-OSC_OUT-Pad6)") (class "Default")
      (node (ref "STM32G474") (pin "6") (pinfunction "PF1-OSC_OUT_6") (pintype "bidirectional+no_connect"))
    )
    (net (code "84") (name "unconnected-(USB_C-SBU1-PadA8)") (class "Default")
      (node (ref "USB_C") (pin "A8") (pinfunction "SBU1_A8") (pintype "passive+no_connect"))
    )
    (net (code "85") (name "unconnected-(USB_C-SBU2-PadB8)") (class "Default")
      (node (ref "USB_C") (pin "B8") (pinfunction "SBU2_B8") (pintype "passive+no_connect"))
    )
  )
)
